# LED_003.net
KiCad netlist of a schematic drawn in EAGLE
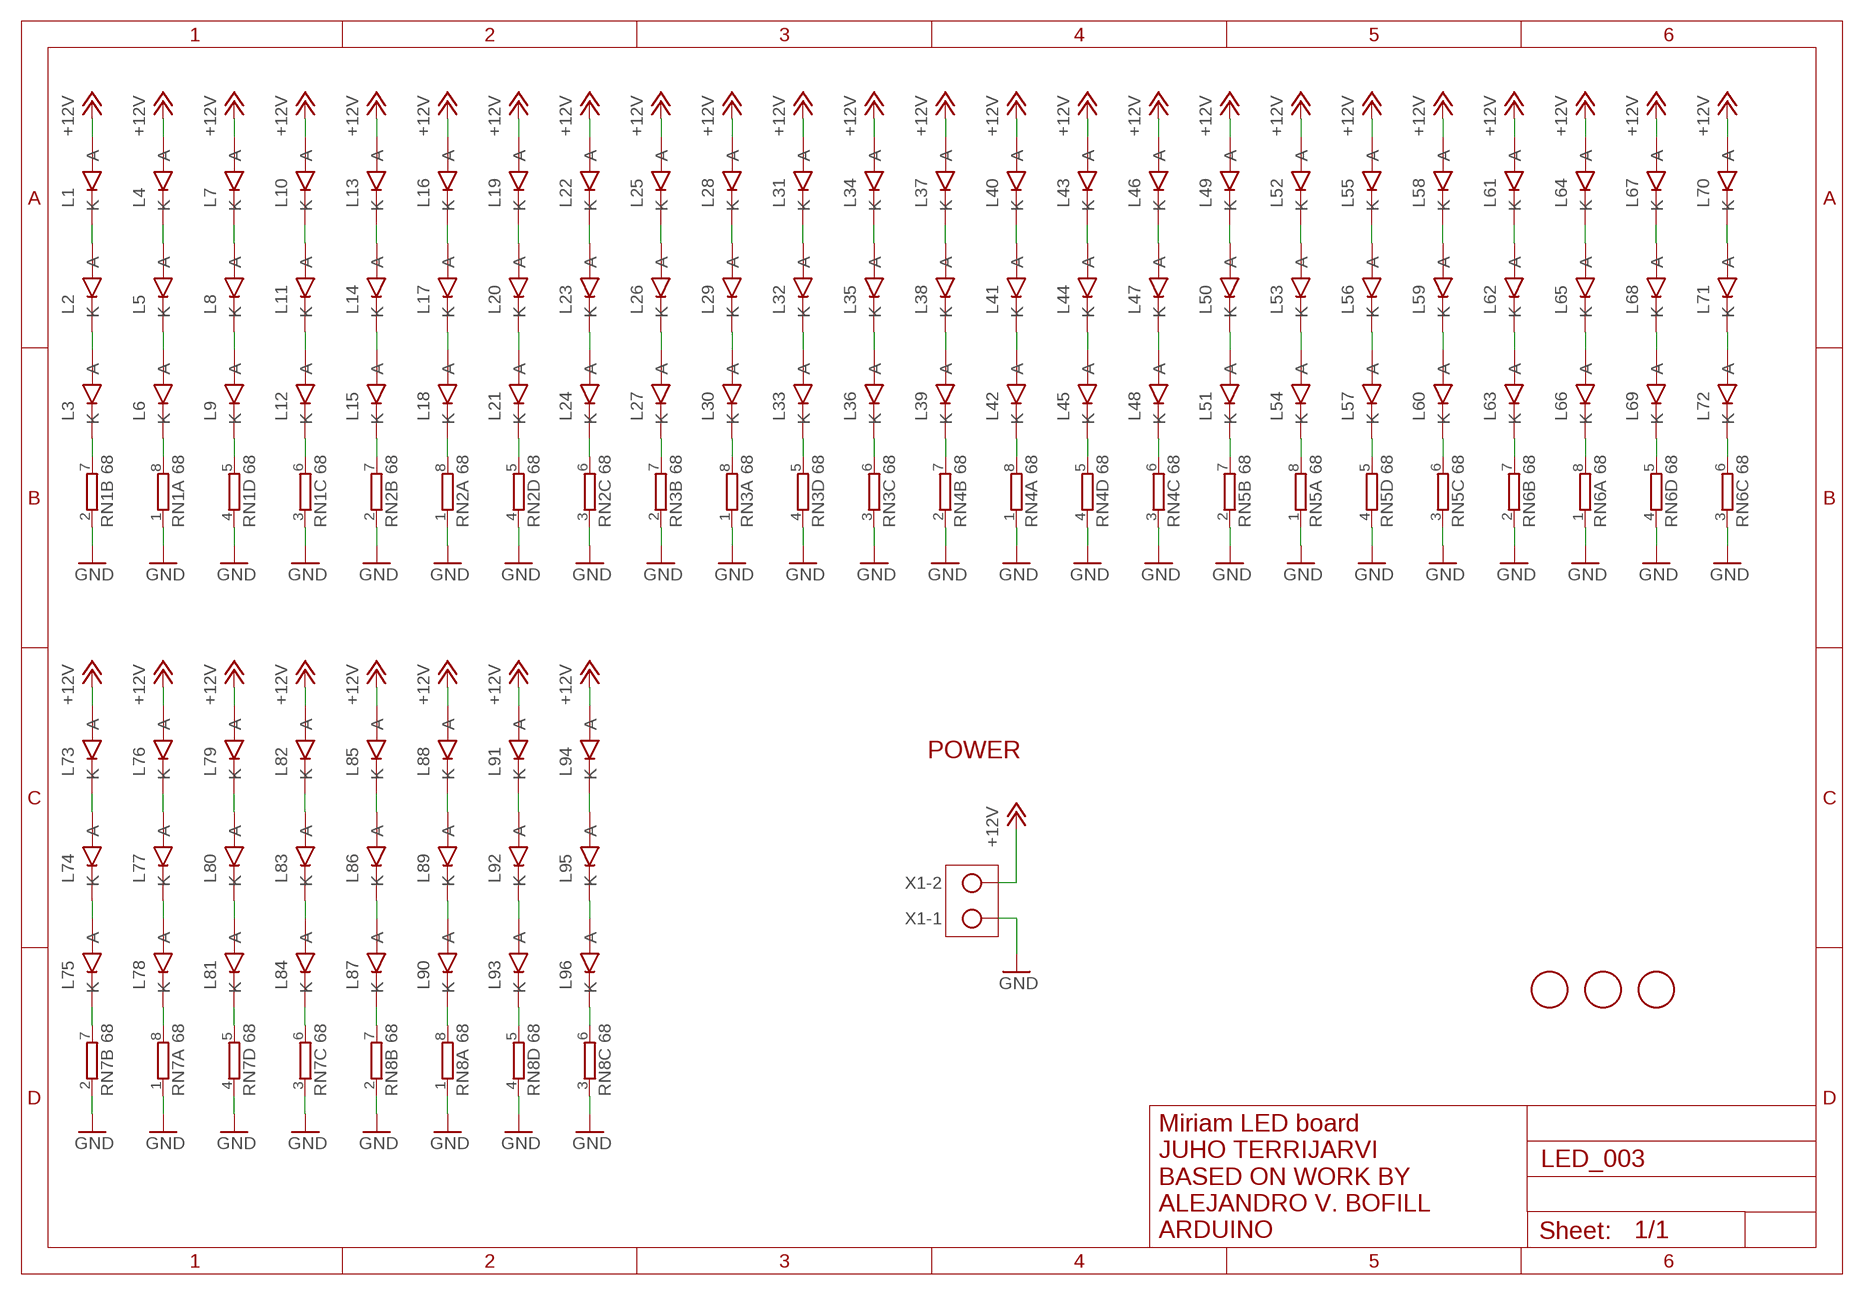
[diagram p0: schematic, sheet 1]

(export (version "E")
  (design (tool "Eeschema 10.0.6"))
  (components
    (comp (ref "FD1")
      (value "FIDUCIALMOUNT")
      (footprint "eagle-import:FIDUCIA-MOUNT")
      (libsource (lib "eagle-import") (part "FIDUCIALMOUNT"))
    )
    (comp (ref "FD2")
      (value "FIDUCIALMOUNT")
      (footprint "eagle-import:FIDUCIA-MOUNT")
      (libsource (lib "eagle-import") (part "FIDUCIALMOUNT"))
    )
    (comp (ref "FD3")
      (value "FIDUCIALMOUNT")
      (footprint "eagle-import:FIDUCIA-MOUNT")
      (libsource (lib "eagle-import") (part "FIDUCIALMOUNT"))
    )
    (comp (ref "L1")
      (value "KA-2810AQBS-G")
      (footprint "eagle-import:LED_0.2")
      (libsource (lib "eagle-import") (part "LED_0.2"))
    )
    (comp (ref "L2")
      (value "KA-2810AQBS-G")
      (footprint "eagle-import:LED_0.2")
      (libsource (lib "eagle-import") (part "LED_0.2"))
    )
    (comp (ref "L3")
      (value "KA-2810AQBS-G")
      (footprint "eagle-import:LED_0.2")
      (libsource (lib "eagle-import") (part "LED_0.2"))
    )
    (comp (ref "L4")
      (value "KA-2810AQBS-G")
      (footprint "eagle-import:LED_0.2")
      (libsource (lib "eagle-import") (part "LED_0.2"))
    )
    (comp (ref "L5")
      (value "KA-2810AQBS-G")
      (footprint "eagle-import:LED_0.2")
      (libsource (lib "eagle-import") (part "LED_0.2"))
    )
    (comp (ref "L6")
      (value "KA-2810AQBS-G")
      (footprint "eagle-import:LED_0.2")
      (libsource (lib "eagle-import") (part "LED_0.2"))
    )
    (comp (ref "L7")
      (value "KA-2810AQBS-G")
      (footprint "eagle-import:LED_0.2")
      (libsource (lib "eagle-import") (part "LED_0.2"))
    )
    (comp (ref "L8")
      (value "KA-2810AQBS-G")
      (footprint "eagle-import:LED_0.2")
      (libsource (lib "eagle-import") (part "LED_0.2"))
    )
    (comp (ref "L9")
      (value "KA-2810AQBS-G")
      (footprint "eagle-import:LED_0.2")
      (libsource (lib "eagle-import") (part "LED_0.2"))
    )
    (comp (ref "L10")
      (value "KA-2810AQBS-G")
      (footprint "eagle-import:LED_0.2")
      (libsource (lib "eagle-import") (part "LED_0.2"))
    )
    (comp (ref "L11")
      (value "KA-2810AQBS-G")
      (footprint "eagle-import:LED_0.2")
      (libsource (lib "eagle-import") (part "LED_0.2"))
    )
    (comp (ref "L12")
      (value "KA-2810AQBS-G")
      (footprint "eagle-import:LED_0.2")
      (libsource (lib "eagle-import") (part "LED_0.2"))
    )
    (comp (ref "L13")
      (value "KA-2810AQBS-G")
      (footprint "eagle-import:LED_0.2")
      (libsource (lib "eagle-import") (part "LED_0.2"))
    )
    (comp (ref "L14")
      (value "KA-2810AQBS-G")
      (footprint "eagle-import:LED_0.2")
      (libsource (lib "eagle-import") (part "LED_0.2"))
    )
    (comp (ref "L15")
      (value "KA-2810AQBS-G")
      (footprint "eagle-import:LED_0.2")
      (libsource (lib "eagle-import") (part "LED_0.2"))
    )
    (comp (ref "L16")
      (value "KA-2810AQBS-G")
      (footprint "eagle-import:LED_0.2")
      (libsource (lib "eagle-import") (part "LED_0.2"))
    )
    (comp (ref "L17")
      (value "KA-2810AQBS-G")
      (footprint "eagle-import:LED_0.2")
      (libsource (lib "eagle-import") (part "LED_0.2"))
    )
    (comp (ref "L18")
      (value "KA-2810AQBS-G")
      (footprint "eagle-import:LED_0.2")
      (libsource (lib "eagle-import") (part "LED_0.2"))
    )
    (comp (ref "L19")
      (value "KA-2810AQBS-G")
      (footprint "eagle-import:LED_0.2")
      (libsource (lib "eagle-import") (part "LED_0.2"))
    )
    (comp (ref "L20")
      (value "KA-2810AQBS-G")
      (footprint "eagle-import:LED_0.2")
      (libsource (lib "eagle-import") (part "LED_0.2"))
    )
    (comp (ref "L21")
      (value "KA-2810AQBS-G")
      (footprint "eagle-import:LED_0.2")
      (libsource (lib "eagle-import") (part "LED_0.2"))
    )
    (comp (ref "L22")
      (value "KA-2810AQBS-G")
      (footprint "eagle-import:LED_0.2")
      (libsource (lib "eagle-import") (part "LED_0.2"))
    )
    (comp (ref "L23")
      (value "KA-2810AQBS-G")
      (footprint "eagle-import:LED_0.2")
      (libsource (lib "eagle-import") (part "LED_0.2"))
    )
    (comp (ref "L24")
      (value "KA-2810AQBS-G")
      (footprint "eagle-import:LED_0.2")
      (libsource (lib "eagle-import") (part "LED_0.2"))
    )
    (comp (ref "L25")
      (value "KA-2810AQBS-G")
      (footprint "eagle-import:LED_0.2")
      (libsource (lib "eagle-import") (part "LED_0.2"))
    )
    (comp (ref "L26")
      (value "KA-2810AQBS-G")
      (footprint "eagle-import:LED_0.2")
      (libsource (lib "eagle-import") (part "LED_0.2"))
    )
    (comp (ref "L27")
      (value "KA-2810AQBS-G")
      (footprint "eagle-import:LED_0.2")
      (libsource (lib "eagle-import") (part "LED_0.2"))
    )
    (comp (ref "L28")
      (value "KA-2810AQBS-G")
      (footprint "eagle-import:LED_0.2")
      (libsource (lib "eagle-import") (part "LED_0.2"))
    )
    (comp (ref "L29")
      (value "KA-2810AQBS-G")
      (footprint "eagle-import:LED_0.2")
      (libsource (lib "eagle-import") (part "LED_0.2"))
    )
    (comp (ref "L30")
      (value "KA-2810AQBS-G")
      (footprint "eagle-import:LED_0.2")
      (libsource (lib "eagle-import") (part "LED_0.2"))
    )
    (comp (ref "L31")
      (value "KA-2810AQBS-G")
      (footprint "eagle-import:LED_0.2")
      (libsource (lib "eagle-import") (part "LED_0.2"))
    )
    (comp (ref "L32")
      (value "KA-2810AQBS-G")
      (footprint "eagle-import:LED_0.2")
      (libsource (lib "eagle-import") (part "LED_0.2"))
    )
    (comp (ref "L33")
      (value "KA-2810AQBS-G")
      (footprint "eagle-import:LED_0.2")
      (libsource (lib "eagle-import") (part "LED_0.2"))
    )
    (comp (ref "L34")
      (value "KA-2810AQBS-G")
      (footprint "eagle-import:LED_0.2")
      (libsource (lib "eagle-import") (part "LED_0.2"))
    )
    (comp (ref "L35")
      (value "KA-2810AQBS-G")
      (footprint "eagle-import:LED_0.2")
      (libsource (lib "eagle-import") (part "LED_0.2"))
    )
    (comp (ref "L36")
      (value "KA-2810AQBS-G")
      (footprint "eagle-import:LED_0.2")
      (libsource (lib "eagle-import") (part "LED_0.2"))
    )
    (comp (ref "L37")
      (value "KA-2810AQBS-G")
      (footprint "eagle-import:LED_0.2")
      (libsource (lib "eagle-import") (part "LED_0.2"))
    )
    (comp (ref "L38")
      (value "KA-2810AQBS-G")
      (footprint "eagle-import:LED_0.2")
      (libsource (lib "eagle-import") (part "LED_0.2"))
    )
    (comp (ref "L39")
      (value "KA-2810AQBS-G")
      (footprint "eagle-import:LED_0.2")
      (libsource (lib "eagle-import") (part "LED_0.2"))
    )
    (comp (ref "L40")
      (value "KA-2810AQBS-G")
      (footprint "eagle-import:LED_0.2")
      (libsource (lib "eagle-import") (part "LED_0.2"))
    )
    (comp (ref "L41")
      (value "KA-2810AQBS-G")
      (footprint "eagle-import:LED_0.2")
      (libsource (lib "eagle-import") (part "LED_0.2"))
    )
    (comp (ref "L42")
      (value "KA-2810AQBS-G")
      (footprint "eagle-import:LED_0.2")
      (libsource (lib "eagle-import") (part "LED_0.2"))
    )
    (comp (ref "L43")
      (value "KA-2810AQBS-G")
      (footprint "eagle-import:LED_0.2")
      (libsource (lib "eagle-import") (part "LED_0.2"))
    )
    (comp (ref "L44")
      (value "KA-2810AQBS-G")
      (footprint "eagle-import:LED_0.2")
      (libsource (lib "eagle-import") (part "LED_0.2"))
    )
    (comp (ref "L45")
      (value "KA-2810AQBS-G")
      (footprint "eagle-import:LED_0.2")
      (libsource (lib "eagle-import") (part "LED_0.2"))
    )
    (comp (ref "L46")
      (value "KA-2810AQBS-G")
      (footprint "eagle-import:LED_0.2")
      (libsource (lib "eagle-import") (part "LED_0.2"))
    )
    (comp (ref "L47")
      (value "KA-2810AQBS-G")
      (footprint "eagle-import:LED_0.2")
      (libsource (lib "eagle-import") (part "LED_0.2"))
    )
    (comp (ref "L48")
      (value "KA-2810AQBS-G")
      (footprint "eagle-import:LED_0.2")
      (libsource (lib "eagle-import") (part "LED_0.2"))
    )
    (comp (ref "L49")
      (value "KA-2810AQBS-G")
      (footprint "eagle-import:LED_0.2")
      (libsource (lib "eagle-import") (part "LED_0.2"))
    )
    (comp (ref "L50")
      (value "KA-2810AQBS-G")
      (footprint "eagle-import:LED_0.2")
      (libsource (lib "eagle-import") (part "LED_0.2"))
    )
    (comp (ref "L51")
      (value "KA-2810AQBS-G")
      (footprint "eagle-import:LED_0.2")
      (libsource (lib "eagle-import") (part "LED_0.2"))
    )
    (comp (ref "L52")
      (value "KA-2810AQBS-G")
      (footprint "eagle-import:LED_0.2")
      (libsource (lib "eagle-import") (part "LED_0.2"))
    )
    (comp (ref "L53")
      (value "KA-2810AQBS-G")
      (footprint "eagle-import:LED_0.2")
      (libsource (lib "eagle-import") (part "LED_0.2"))
    )
    (comp (ref "L54")
      (value "KA-2810AQBS-G")
      (footprint "eagle-import:LED_0.2")
      (libsource (lib "eagle-import") (part "LED_0.2"))
    )
    (comp (ref "L55")
      (value "KA-2810AQBS-G")
      (footprint "eagle-import:LED_0.2")
      (libsource (lib "eagle-import") (part "LED_0.2"))
    )
    (comp (ref "L56")
      (value "KA-2810AQBS-G")
      (footprint "eagle-import:LED_0.2")
      (libsource (lib "eagle-import") (part "LED_0.2"))
    )
    (comp (ref "L57")
      (value "KA-2810AQBS-G")
      (footprint "eagle-import:LED_0.2")
      (libsource (lib "eagle-import") (part "LED_0.2"))
    )
    (comp (ref "L58")
      (value "KA-2810AQBS-G")
      (footprint "eagle-import:LED_0.2")
      (libsource (lib "eagle-import") (part "LED_0.2"))
    )
    (comp (ref "L59")
      (value "KA-2810AQBS-G")
      (footprint "eagle-import:LED_0.2")
      (libsource (lib "eagle-import") (part "LED_0.2"))
    )
    (comp (ref "L60")
      (value "KA-2810AQBS-G")
      (footprint "eagle-import:LED_0.2")
      (libsource (lib "eagle-import") (part "LED_0.2"))
    )
    (comp (ref "L61")
      (value "KA-2810AQBS-G")
      (footprint "eagle-import:LED_0.2")
      (libsource (lib "eagle-import") (part "LED_0.2"))
    )
    (comp (ref "L62")
      (value "KA-2810AQBS-G")
      (footprint "eagle-import:LED_0.2")
      (libsource (lib "eagle-import") (part "LED_0.2"))
    )
    (comp (ref "L63")
      (value "KA-2810AQBS-G")
      (footprint "eagle-import:LED_0.2")
      (libsource (lib "eagle-import") (part "LED_0.2"))
    )
    (comp (ref "L64")
      (value "KA-2810AQBS-G")
      (footprint "eagle-import:LED_0.2")
      (libsource (lib "eagle-import") (part "LED_0.2"))
    )
    (comp (ref "L65")
      (value "KA-2810AQBS-G")
      (footprint "eagle-import:LED_0.2")
      (libsource (lib "eagle-import") (part "LED_0.2"))
    )
    (comp (ref "L66")
      (value "KA-2810AQBS-G")
      (footprint "eagle-import:LED_0.2")
      (libsource (lib "eagle-import") (part "LED_0.2"))
    )
    (comp (ref "L67")
      (value "KA-2810AQBS-G")
      (footprint "eagle-import:LED_0.2")
      (libsource (lib "eagle-import") (part "LED_0.2"))
    )
    (comp (ref "L68")
      (value "KA-2810AQBS-G")
      (footprint "eagle-import:LED_0.2")
      (libsource (lib "eagle-import") (part "LED_0.2"))
    )
    (comp (ref "L69")
      (value "KA-2810AQBS-G")
      (footprint "eagle-import:LED_0.2")
      (libsource (lib "eagle-import") (part "LED_0.2"))
    )
    (comp (ref "L70")
      (value "KA-2810AQBS-G")
      (footprint "eagle-import:LED_0.2")
      (libsource (lib "eagle-import") (part "LED_0.2"))
    )
    (comp (ref "L71")
      (value "KA-2810AQBS-G")
      (footprint "eagle-import:LED_0.2")
      (libsource (lib "eagle-import") (part "LED_0.2"))
    )
    (comp (ref "L72")
      (value "KA-2810AQBS-G")
      (footprint "eagle-import:LED_0.2")
      (libsource (lib "eagle-import") (part "LED_0.2"))
    )
    (comp (ref "L73")
      (value "KA-2810AQBS-G")
      (footprint "eagle-import:LED_0.2")
      (libsource (lib "eagle-import") (part "LED_0.2"))
    )
    (comp (ref "L74")
      (value "KA-2810AQBS-G")
      (footprint "eagle-import:LED_0.2")
      (libsource (lib "eagle-import") (part "LED_0.2"))
    )
    (comp (ref "L75")
      (value "KA-2810AQBS-G")
      (footprint "eagle-import:LED_0.2")
      (libsource (lib "eagle-import") (part "LED_0.2"))
    )
    (comp (ref "L76")
      (value "KA-2810AQBS-G")
      (footprint "eagle-import:LED_0.2")
      (libsource (lib "eagle-import") (part "LED_0.2"))
    )
    (comp (ref "L77")
      (value "KA-2810AQBS-G")
      (footprint "eagle-import:LED_0.2")
      (libsource (lib "eagle-import") (part "LED_0.2"))
    )
    (comp (ref "L78")
      (value "KA-2810AQBS-G")
      (footprint "eagle-import:LED_0.2")
      (libsource (lib "eagle-import") (part "LED_0.2"))
    )
    (comp (ref "L79")
      (value "KA-2810AQBS-G")
      (footprint "eagle-import:LED_0.2")
      (libsource (lib "eagle-import") (part "LED_0.2"))
    )
    (comp (ref "L80")
      (value "KA-2810AQBS-G")
      (footprint "eagle-import:LED_0.2")
      (libsource (lib "eagle-import") (part "LED_0.2"))
    )
    (comp (ref "L81")
      (value "KA-2810AQBS-G")
      (footprint "eagle-import:LED_0.2")
      (libsource (lib "eagle-import") (part "LED_0.2"))
    )
    (comp (ref "L82")
      (value "KA-2810AQBS-G")
      (footprint "eagle-import:LED_0.2")
      (libsource (lib "eagle-import") (part "LED_0.2"))
    )
    (comp (ref "L83")
      (value "KA-2810AQBS-G")
      (footprint "eagle-import:LED_0.2")
      (libsource (lib "eagle-import") (part "LED_0.2"))
    )
    (comp (ref "L84")
      (value "KA-2810AQBS-G")
      (footprint "eagle-import:LED_0.2")
      (libsource (lib "eagle-import") (part "LED_0.2"))
    )
    (comp (ref "L85")
      (value "KA-2810AQBS-G")
      (footprint "eagle-import:LED_0.2")
      (libsource (lib "eagle-import") (part "LED_0.2"))
    )
    (comp (ref "L86")
      (value "KA-2810AQBS-G")
      (footprint "eagle-import:LED_0.2")
      (libsource (lib "eagle-import") (part "LED_0.2"))
    )
    (comp (ref "L87")
      (value "KA-2810AQBS-G")
      (footprint "eagle-import:LED_0.2")
      (libsource (lib "eagle-import") (part "LED_0.2"))
    )
    (comp (ref "L88")
      (value "KA-2810AQBS-G")
      (footprint "eagle-import:LED_0.2")
      (libsource (lib "eagle-import") (part "LED_0.2"))
    )
    (comp (ref "L89")
      (value "KA-2810AQBS-G")
      (footprint "eagle-import:LED_0.2")
      (libsource (lib "eagle-import") (part "LED_0.2"))
    )
    (comp (ref "L90")
      (value "KA-2810AQBS-G")
      (footprint "eagle-import:LED_0.2")
      (libsource (lib "eagle-import") (part "LED_0.2"))
    )
    (comp (ref "L91")
      (value "KA-2810AQBS-G")
      (footprint "eagle-import:LED_0.2")
      (libsource (lib "eagle-import") (part "LED_0.2"))
    )
    (comp (ref "L92")
      (value "KA-2810AQBS-G")
      (footprint "eagle-import:LED_0.2")
      (libsource (lib "eagle-import") (part "LED_0.2"))
    )
    (comp (ref "L93")
      (value "KA-2810AQBS-G")
      (footprint "eagle-import:LED_0.2")
      (libsource (lib "eagle-import") (part "LED_0.2"))
    )
    (comp (ref "L94")
      (value "KA-2810AQBS-G")
      (footprint "eagle-import:LED_0.2")
      (libsource (lib "eagle-import") (part "LED_0.2"))
    )
    (comp (ref "L95")
      (value "KA-2810AQBS-G")
      (footprint "eagle-import:LED_0.2")
      (libsource (lib "eagle-import") (part "LED_0.2"))
    )
    (comp (ref "L96")
      (value "KA-2810AQBS-G")
      (footprint "eagle-import:LED_0.2")
      (libsource (lib "eagle-import") (part "LED_0.2"))
    )
    (comp (ref "RN1")
      (value "68")
      (footprint "eagle-import:CAY16")
      (libsource (lib "eagle-import") (part "4R-NCAY16"))
    )
    (comp (ref "RN2")
      (value "68")
      (footprint "eagle-import:CAY16")
      (libsource (lib "eagle-import") (part "4R-NCAY16"))
    )
    (comp (ref "RN3")
      (value "68")
      (footprint "eagle-import:CAY16")
      (libsource (lib "eagle-import") (part "4R-NCAY16"))
    )
    (comp (ref "RN4")
      (value "68")
      (footprint "eagle-import:CAY16")
      (libsource (lib "eagle-import") (part "4R-NCAY16"))
    )
    (comp (ref "RN5")
      (value "68")
      (footprint "eagle-import:CAY16")
      (libsource (lib "eagle-import") (part "4R-NCAY16"))
    )
    (comp (ref "RN6")
      (value "68")
      (footprint "eagle-import:CAY16")
      (libsource (lib "eagle-import") (part "4R-NCAY16"))
    )
    (comp (ref "RN7")
      (value "68")
      (footprint "eagle-import:CAY16")
      (libsource (lib "eagle-import") (part "4R-NCAY16"))
    )
    (comp (ref "RN8")
      (value "68")
      (footprint "eagle-import:CAY16")
      (libsource (lib "eagle-import") (part "4R-NCAY16"))
    )
    (comp (ref "X1")
      (value "MKDSN1,5/2-5,08")
      (footprint "eagle-import:MKDSN1,5_2-5,08")
      (libsource (lib "eagle-import") (part "MKDSN1,5/2-5,08"))
    )
  )
  (nets
    (net (code "1") (name "+12V") (class "Default")
      (node (ref "L1") (pin "2") (pinfunction "A_2") (pintype "input"))
      (node (ref "L10") (pin "2") (pinfunction "A_2") (pintype "input"))
      (node (ref "L13") (pin "2") (pinfunction "A_2") (pintype "input"))
      (node (ref "L16") (pin "2") (pinfunction "A_2") (pintype "input"))
      (node (ref "L19") (pin "2") (pinfunction "A_2") (pintype "input"))
      (node (ref "L22") (pin "2") (pinfunction "A_2") (pintype "input"))
      (node (ref "L25") (pin "2") (pinfunction "A_2") (pintype "input"))
      (node (ref "L28") (pin "2") (pinfunction "A_2") (pintype "input"))
      (node (ref "L31") (pin "2") (pinfunction "A_2") (pintype "input"))
      (node (ref "L34") (pin "2") (pinfunction "A_2") (pintype "input"))
      (node (ref "L37") (pin "2") (pinfunction "A_2") (pintype "input"))
      (node (ref "L4") (pin "2") (pinfunction "A_2") (pintype "input"))
      (node (ref "L40") (pin "2") (pinfunction "A_2") (pintype "input"))
      (node (ref "L43") (pin "2") (pinfunction "A_2") (pintype "input"))
      (node (ref "L46") (pin "2") (pinfunction "A_2") (pintype "input"))
      (node (ref "L49") (pin "2") (pinfunction "A_2") (pintype "input"))
      (node (ref "L52") (pin "2") (pinfunction "A_2") (pintype "input"))
      (node (ref "L55") (pin "2") (pinfunction "A_2") (pintype "input"))
      (node (ref "L58") (pin "2") (pinfunction "A_2") (pintype "input"))
      (node (ref "L61") (pin "2") (pinfunction "A_2") (pintype "input"))
      (node (ref "L64") (pin "2") (pinfunction "A_2") (pintype "input"))
      (node (ref "L67") (pin "2") (pinfunction "A_2") (pintype "input"))
      (node (ref "L7") (pin "2") (pinfunction "A_2") (pintype "input"))
      (node (ref "L70") (pin "2") (pinfunction "A_2") (pintype "input"))
      (node (ref "L73") (pin "2") (pinfunction "A_2") (pintype "input"))
      (node (ref "L76") (pin "2") (pinfunction "A_2") (pintype "input"))
      (node (ref "L79") (pin "2") (pinfunction "A_2") (pintype "input"))
      (node (ref "L82") (pin "2") (pinfunction "A_2") (pintype "input"))
      (node (ref "L85") (pin "2") (pinfunction "A_2") (pintype "input"))
      (node (ref "L88") (pin "2") (pinfunction "A_2") (pintype "input"))
      (node (ref "L91") (pin "2") (pinfunction "A_2") (pintype "input"))
      (node (ref "L94") (pin "2") (pinfunction "A_2") (pintype "input"))
      (node (ref "X1") (pin "2") (pinfunction "KL_2") (pintype "passive"))
    )
    (net (code "2") (name "GND") (class "Default")
      (node (ref "RN1") (pin "1") (pinfunction "1_1") (pintype "passive"))
      (node (ref "RN1") (pin "2") (pinfunction "1_2") (pintype "passive"))
      (node (ref "RN1") (pin "3") (pinfunction "1_3") (pintype "passive"))
      (node (ref "RN1") (pin "4") (pinfunction "1_4") (pintype "passive"))
      (node (ref "RN2") (pin "1") (pinfunction "1_1") (pintype "passive"))
      (node (ref "RN2") (pin "2") (pinfunction "1_2") (pintype "passive"))
      (node (ref "RN2") (pin "3") (pinfunction "1_3") (pintype "passive"))
      (node (ref "RN2") (pin "4") (pinfunction "1_4") (pintype "passive"))
      (node (ref "RN3") (pin "1") (pinfunction "1_1") (pintype "passive"))
      (node (ref "RN3") (pin "2") (pinfunction "1_2") (pintype "passive"))
      (node (ref "RN3") (pin "3") (pinfunction "1_3") (pintype "passive"))
      (node (ref "RN3") (pin "4") (pinfunction "1_4") (pintype "passive"))
      (node (ref "RN4") (pin "1") (pinfunction "1_1") (pintype "passive"))
      (node (ref "RN4") (pin "2") (pinfunction "1_2") (pintype "passive"))
      (node (ref "RN4") (pin "3") (pinfunction "1_3") (pintype "passive"))
      (node (ref "RN4") (pin "4") (pinfunction "1_4") (pintype "passive"))
      (node (ref "RN5") (pin "1") (pinfunction "1_1") (pintype "passive"))
      (node (ref "RN5") (pin "2") (pinfunction "1_2") (pintype "passive"))
      (node (ref "RN5") (pin "3") (pinfunction "1_3") (pintype "passive"))
      (node (ref "RN5") (pin "4") (pinfunction "1_4") (pintype "passive"))
      (node (ref "RN6") (pin "1") (pinfunction "1_1") (pintype "passive"))
      (node (ref "RN6") (pin "2") (pinfunction "1_2") (pintype "passive"))
      (node (ref "RN6") (pin "3") (pinfunction "1_3") (pintype "passive"))
      (node (ref "RN6") (pin "4") (pinfunction "1_4") (pintype "passive"))
      (node (ref "RN7") (pin "1") (pinfunction "1_1") (pintype "passive"))
      (node (ref "RN7") (pin "2") (pinfunction "1_2") (pintype "passive"))
      (node (ref "RN7") (pin "3") (pinfunction "1_3") (pintype "passive"))
      (node (ref "RN7") (pin "4") (pinfunction "1_4") (pintype "passive"))
      (node (ref "RN8") (pin "1") (pinfunction "1_1") (pintype "passive"))
      (node (ref "RN8") (pin "2") (pinfunction "1_2") (pintype "passive"))
      (node (ref "RN8") (pin "3") (pinfunction "1_3") (pintype "passive"))
      (node (ref "RN8") (pin "4") (pinfunction "1_4") (pintype "passive"))
      (node (ref "X1") (pin "1") (pinfunction "KL_1") (pintype "passive"))
    )
    (net (code "3") (name "Net-(L1-K)") (class "Default")
      (node (ref "L1") (pin "1") (pinfunction "K_1") (pintype "output"))
      (node (ref "L2") (pin "2") (pinfunction "A_2") (pintype "input"))
    )
    (net (code "4") (name "Net-(L2-K)") (class "Default")
      (node (ref "L2") (pin "1") (pinfunction "K_1") (pintype "output"))
      (node (ref "L3") (pin "2") (pinfunction "A_2") (pintype "input"))
    )
    (net (code "5") (name "Net-(L3-K)") (class "Default")
      (node (ref "L3") (pin "1") (pinfunction "K_1") (pintype "output"))
      (node (ref "RN1") (pin "7") (pinfunction "2_7") (pintype "passive"))
    )
    (net (code "6") (name "Net-(L4-K)") (class "Default")
      (node (ref "L4") (pin "1") (pinfunction "K_1") (pintype "output"))
      (node (ref "L5") (pin "2") (pinfunction "A_2") (pintype "input"))
    )
    (net (code "7") (name "Net-(L5-K)") (class "Default")
      (node (ref "L5") (pin "1") (pinfunction "K_1") (pintype "output"))
      (node (ref "L6") (pin "2") (pinfunction "A_2") (pintype "input"))
    )
    (net (code "8") (name "Net-(L6-K)") (class "Default")
      (node (ref "L6") (pin "1") (pinfunction "K_1") (pintype "output"))
      (node (ref "RN1") (pin "8") (pinfunction "2_8") (pintype "passive"))
    )
    (net (code "9") (name "Net-(L7-K)") (class "Default")
      (node (ref "L7") (pin "1") (pinfunction "K_1") (pintype "output"))
      (node (ref "L8") (pin "2") (pinfunction "A_2") (pintype "input"))
    )
    (net (code "10") (name "Net-(L8-K)") (class "Default")
      (node (ref "L8") (pin "1") (pinfunction "K_1") (pintype "output"))
      (node (ref "L9") (pin "2") (pinfunction "A_2") (pintype "input"))
    )
    (net (code "11") (name "Net-(L9-K)") (class "Default")
      (node (ref "L9") (pin "1") (pinfunction "K_1") (pintype "output"))
      (node (ref "RN1") (pin "5") (pinfunction "2_5") (pintype "passive"))
    )
    (net (code "12") (name "Net-(L10-K)") (class "Default")
      (node (ref "L10") (pin "1") (pinfunction "K_1") (pintype "output"))
      (node (ref "L11") (pin "2") (pinfunction "A_2") (pintype "input"))
    )
    (net (code "13") (name "Net-(L11-K)") (class "Default")
      (node (ref "L11") (pin "1") (pinfunction "K_1") (pintype "output"))
      (node (ref "L12") (pin "2") (pinfunction "A_2") (pintype "input"))
    )
    (net (code "14") (name "Net-(L12-K)") (class "Default")
      (node (ref "L12") (pin "1") (pinfunction "K_1") (pintype "output"))
      (node (ref "RN1") (pin "6") (pinfunction "2_6") (pintype "passive"))
    )
    (net (code "15") (name "Net-(L13-K)") (class "Default")
      (node (ref "L13") (pin "1") (pinfunction "K_1") (pintype "output"))
      (node (ref "L14") (pin "2") (pinfunction "A_2") (pintype "input"))
    )
    (net (code "16") (name "Net-(L14-K)") (class "Default")
      (node (ref "L14") (pin "1") (pinfunction "K_1") (pintype "output"))
      (node (ref "L15") (pin "2") (pinfunction "A_2") (pintype "input"))
    )
    (net (code "17") (name "Net-(L15-K)") (class "Default")
      (node (ref "L15") (pin "1") (pinfunction "K_1") (pintype "output"))
      (node (ref "RN2") (pin "7") (pinfunction "2_7") (pintype "passive"))
    )
    (net (code "18") (name "Net-(L16-K)") (class "Default")
      (node (ref "L16") (pin "1") (pinfunction "K_1") (pintype "output"))
      (node (ref "L17") (pin "2") (pinfunction "A_2") (pintype "input"))
    )
    (net (code "19") (name "Net-(L17-K)") (class "Default")
      (node (ref "L17") (pin "1") (pinfunction "K_1") (pintype "output"))
      (node (ref "L18") (pin "2") (pinfunction "A_2") (pintype "input"))
    )
    (net (code "20") (name "Net-(L18-K)") (class "Default")
      (node (ref "L18") (pin "1") (pinfunction "K_1") (pintype "output"))
      (node (ref "RN2") (pin "8") (pinfunction "2_8") (pintype "passive"))
    )
    (net (code "21") (name "Net-(L19-K)") (class "Default")
      (node (ref "L19") (pin "1") (pinfunction "K_1") (pintype "output"))
      (node (ref "L20") (pin "2") (pinfunction "A_2") (pintype "input"))
    )
    (net (code "22") (name "Net-(L20-K)") (class "Default")
      (node (ref "L20") (pin "1") (pinfunction "K_1") (pintype "output"))
      (node (ref "L21") (pin "2") (pinfunction "A_2") (pintype "input"))
    )
    (net (code "23") (name "Net-(L21-K)") (class "Default")
      (node (ref "L21") (pin "1") (pinfunction "K_1") (pintype "output"))
      (node (ref "RN2") (pin "5") (pinfunction "2_5") (pintype "passive"))
    )
    (net (code "24") (name "Net-(L22-K)") (class "Default")
      (node (ref "L22") (pin "1") (pinfunction "K_1") (pintype "output"))
      (node (ref "L23") (pin "2") (pinfunction "A_2") (pintype "input"))
    )
    (net (code "25") (name "Net-(L23-K)") (class "Default")
      (node (ref "L23") (pin "1") (pinfunction "K_1") (pintype "output"))
      (node (ref "L24") (pin "2") (pinfunction "A_2") (pintype "input"))
    )
    (net (code "26") (name "Net-(L24-K)") (class "Default")
      (node (ref "L24") (pin "1") (pinfunction "K_1") (pintype "output"))
      (node (ref "RN2") (pin "6") (pinfunction "2_6") (pintype "passive"))
    )
    (net (code "27") (name "Net-(L25-K)") (class "Default")
      (node (ref "L25") (pin "1") (pinfunction "K_1") (pintype "output"))
      (node (ref "L26") (pin "2") (pinfunction "A_2") (pintype "input"))
    )
    (net (code "28") (name "Net-(L26-K)") (class "Default")
      (node (ref "L26") (pin "1") (pinfunction "K_1") (pintype "output"))
      (node (ref "L27") (pin "2") (pinfunction "A_2") (pintype "input"))
    )
    (net (code "29") (name "Net-(L27-K)") (class "Default")
      (node (ref "L27") (pin "1") (pinfunction "K_1") (pintype "output"))
      (node (ref "RN3") (pin "7") (pinfunction "2_7") (pintype "passive"))
    )
    (net (code "30") (name "Net-(L28-K)") (class "Default")
      (node (ref "L28") (pin "1") (pinfunction "K_1") (pintype "output"))
      (node (ref "L29") (pin "2") (pinfunction "A_2") (pintype "input"))
    )
    (net (code "31") (name "Net-(L29-K)") (class "Default")
      (node (ref "L29") (pin "1") (pinfunction "K_1") (pintype "output"))
      (node (ref "L30") (pin "2") (pinfunction "A_2") (pintype "input"))
    )
    (net (code "32") (name "Net-(L30-K)") (class "Default")
      (node (ref "L30") (pin "1") (pinfunction "K_1") (pintype "output"))
      (node (ref "RN3") (pin "8") (pinfunction "2_8") (pintype "passive"))
    )
    (net (code "33") (name "Net-(L31-K)") (class "Default")
      (node (ref "L31") (pin "1") (pinfunction "K_1") (pintype "output"))
      (node (ref "L32") (pin "2") (pinfunction "A_2") (pintype "input"))
    )
    (net (code "34") (name "Net-(L32-K)") (class "Default")
      (node (ref "L32") (pin "1") (pinfunction "K_1") (pintype "output"))
      (node (ref "L33") (pin "2") (pinfunction "A_2") (pintype "input"))
    )
    (net (code "35") (name "Net-(L33-K)") (class "Default")
      (node (ref "L33") (pin "1") (pinfunction "K_1") (pintype "output"))
      (node (ref "RN3") (pin "5") (pinfunction "2_5") (pintype "passive"))
    )
    (net (code "36") (name "Net-(L34-K)") (class "Default")
      (node (ref "L34") (pin "1") (pinfunction "K_1") (pintype "output"))
      (node (ref "L35") (pin "2") (pinfunction "A_2") (pintype "input"))
    )
    (net (code "37") (name "Net-(L35-K)") (class "Default")
      (node (ref "L35") (pin "1") (pinfunction "K_1") (pintype "output"))
      (node (ref "L36") (pin "2") (pinfunction "A_2") (pintype "input"))
    )
    (net (code "38") (name "Net-(L36-K)") (class "Default")
      (node (ref "L36") (pin "1") (pinfunction "K_1") (pintype "output"))
      (node (ref "RN3") (pin "6") (pinfunction "2_6") (pintype "passive"))
    )
    (net (code "39") (name "Net-(L37-K)") (class "Default")
      (node (ref "L37") (pin "1") (pinfunction "K_1") (pintype "output"))
      (node (ref "L38") (pin "2") (pinfunction "A_2") (pintype "input"))
    )
    (net (code "40") (name "Net-(L38-K)") (class "Default")
      (node (ref "L38") (pin "1") (pinfunction "K_1") (pintype "output"))
      (node (ref "L39") (pin "2") (pinfunction "A_2") (pintype "input"))
    )
    (net (code "41") (name "Net-(L39-K)") (class "Default")
      (node (ref "L39") (pin "1") (pinfunction "K_1") (pintype "output"))
      (node (ref "RN4") (pin "7") (pinfunction "2_7") (pintype "passive"))
    )
    (net (code "42") (name "Net-(L40-K)") (class "Default")
      (node (ref "L40") (pin "1") (pinfunction "K_1") (pintype "output"))
      (node (ref "L41") (pin "2") (pinfunction "A_2") (pintype "input"))
    )
    (net (code "43") (name "Net-(L41-K)") (class "Default")
      (node (ref "L41") (pin "1") (pinfunction "K_1") (pintype "output"))
      (node (ref "L42") (pin "2") (pinfunction "A_2") (pintype "input"))
    )
    (net (code "44") (name "Net-(L42-K)") (class "Default")
      (node (ref "L42") (pin "1") (pinfunction "K_1") (pintype "output"))
      (node (ref "RN4") (pin "8") (pinfunction "2_8") (pintype "passive"))
    )
    (net (code "45") (name "Net-(L43-K)") (class "Default")
      (node (ref "L43") (pin "1") (pinfunction "K_1") (pintype "output"))
      (node (ref "L44") (pin "2") (pinfunction "A_2") (pintype "input"))
    )
    (net (code "46") (name "Net-(L44-K)") (class "Default")
      (node (ref "L44") (pin "1") (pinfunction "K_1") (pintype "output"))
      (node (ref "L45") (pin "2") (pinfunction "A_2") (pintype "input"))
    )
    (net (code "47") (name "Net-(L45-K)") (class "Default")
      (node (ref "L45") (pin "1") (pinfunction "K_1") (pintype "output"))
      (node (ref "RN4") (pin "5") (pinfunction "2_5") (pintype "passive"))
    )
    (net (code "48") (name "Net-(L46-K)") (class "Default")
      (node (ref "L46") (pin "1") (pinfunction "K_1") (pintype "output"))
      (node (ref "L47") (pin "2") (pinfunction "A_2") (pintype "input"))
    )
    (net (code "49") (name "Net-(L47-K)") (class "Default")
      (node (ref "L47") (pin "1") (pinfunction "K_1") (pintype "output"))
      (node (ref "L48") (pin "2") (pinfunction "A_2") (pintype "input"))
    )
    (net (code "50") (name "Net-(L48-K)") (class "Default")
      (node (ref "L48") (pin "1") (pinfunction "K_1") (pintype "output"))
      (node (ref "RN4") (pin "6") (pinfunction "2_6") (pintype "passive"))
    )
    (net (code "51") (name "Net-(L49-K)") (class "Default")
      (node (ref "L49") (pin "1") (pinfunction "K_1") (pintype "output"))
      (node (ref "L50") (pin "2") (pinfunction "A_2") (pintype "input"))
    )
    (net (code "52") (name "Net-(L50-K)") (class "Default")
      (node (ref "L50") (pin "1") (pinfunction "K_1") (pintype "output"))
      (node (ref "L51") (pin "2") (pinfunction "A_2") (pintype "input"))
    )
    (net (code "53") (name "Net-(L51-K)") (class "Default")
      (node (ref "L51") (pin "1") (pinfunction "K_1") (pintype "output"))
      (node (ref "RN5") (pin "7") (pinfunction "2_7") (pintype "passive"))
    )
    (net (code "54") (name "Net-(L52-K)") (class "Default")
      (node (ref "L52") (pin "1") (pinfunction "K_1") (pintype "output"))
      (node (ref "L53") (pin "2") (pinfunction "A_2") (pintype "input"))
    )
    (net (code "55") (name "Net-(L53-K)") (class "Default")
      (node (ref "L53") (pin "1") (pinfunction "K_1") (pintype "output"))
      (node (ref "L54") (pin "2") (pinfunction "A_2") (pintype "input"))
    )
    (net (code "56") (name "Net-(L54-K)") (class "Default")
      (node (ref "L54") (pin "1") (pinfunction "K_1") (pintype "output"))
      (node (ref "RN5") (pin "8") (pinfunction "2_8") (pintype "passive"))
    )
    (net (code "57") (name "Net-(L55-K)") (class "Default")
      (node (ref "L55") (pin "1") (pinfunction "K_1") (pintype "output"))
      (node (ref "L56") (pin "2") (pinfunction "A_2") (pintype "input"))
    )
    (net (code "58") (name "Net-(L56-K)") (class "Default")
      (node (ref "L56") (pin "1") (pinfunction "K_1") (pintype "output"))
      (node (ref "L57") (pin "2") (pinfunction "A_2") (pintype "input"))
    )
    (net (code "59") (name "Net-(L57-K)") (class "Default")
      (node (ref "L57") (pin "1") (pinfunction "K_1") (pintype "output"))
      (node (ref "RN5") (pin "5") (pinfunction "2_5") (pintype "passive"))
    )
    (net (code "60") (name "Net-(L58-K)") (class "Default")
      (node (ref "L58") (pin "1") (pinfunction "K_1") (pintype "output"))
      (node (ref "L59") (pin "2") (pinfunction "A_2") (pintype "input"))
    )
    (net (code "61") (name "Net-(L59-K)") (class "Default")
      (node (ref "L59") (pin "1") (pinfunction "K_1") (pintype "output"))
      (node (ref "L60") (pin "2") (pinfunction "A_2") (pintype "input"))
    )
    (net (code "62") (name "Net-(L60-K)") (class "Default")
      (node (ref "L60") (pin "1") (pinfunction "K_1") (pintype "output"))
      (node (ref "RN5") (pin "6") (pinfunction "2_6") (pintype "passive"))
    )
    (net (code "63") (name "Net-(L61-K)") (class "Default")
      (node (ref "L61") (pin "1") (pinfunction "K_1") (pintype "output"))
      (node (ref "L62") (pin "2") (pinfunction "A_2") (pintype "input"))
    )
    (net (code "64") (name "Net-(L62-K)") (class "Default")
      (node (ref "L62") (pin "1") (pinfunction "K_1") (pintype "output"))
      (node (ref "L63") (pin "2") (pinfunction "A_2") (pintype "input"))
    )
    (net (code "65") (name "Net-(L63-K)") (class "Default")
      (node (ref "L63") (pin "1") (pinfunction "K_1") (pintype "output"))
      (node (ref "RN6") (pin "7") (pinfunction "2_7") (pintype "passive"))
    )
    (net (code "66") (name "Net-(L64-K)") (class "Default")
      (node (ref "L64") (pin "1") (pinfunction "K_1") (pintype "output"))
      (node (ref "L65") (pin "2") (pinfunction "A_2") (pintype "input"))
    )
    (net (code "67") (name "Net-(L65-K)") (class "Default")
      (node (ref "L65") (pin "1") (pinfunction "K_1") (pintype "output"))
      (node (ref "L66") (pin "2") (pinfunction "A_2") (pintype "input"))
    )
    (net (code "68") (name "Net-(L66-K)") (class "Default")
      (node (ref "L66") (pin "1") (pinfunction "K_1") (pintype "output"))
      (node (ref "RN6") (pin "8") (pinfunction "2_8") (pintype "passive"))
    )
    (net (code "69") (name "Net-(L67-K)") (class "Default")
      (node (ref "L67") (pin "1") (pinfunction "K_1") (pintype "output"))
      (node (ref "L68") (pin "2") (pinfunction "A_2") (pintype "input"))
    )
    (net (code "70") (name "Net-(L68-K)") (class "Default")
      (node (ref "L68") (pin "1") (pinfunction "K_1") (pintype "output"))
      (node (ref "L69") (pin "2") (pinfunction "A_2") (pintype "input"))
    )
    (net (code "71") (name "Net-(L69-K)") (class "Default")
      (node (ref "L69") (pin "1") (pinfunction "K_1") (pintype "output"))
      (node (ref "RN6") (pin "5") (pinfunction "2_5") (pintype "passive"))
    )
    (net (code "72") (name "Net-(L70-K)") (class "Default")
      (node (ref "L70") (pin "1") (pinfunction "K_1") (pintype "output"))
      (node (ref "L71") (pin "2") (pinfunction "A_2") (pintype "input"))
    )
    (net (code "73") (name "Net-(L71-K)") (class "Default")
      (node (ref "L71") (pin "1") (pinfunction "K_1") (pintype "output"))
      (node (ref "L72") (pin "2") (pinfunction "A_2") (pintype "input"))
    )
    (net (code "74") (name "Net-(L72-K)") (class "Default")
      (node (ref "L72") (pin "1") (pinfunction "K_1") (pintype "output"))
      (node (ref "RN6") (pin "6") (pinfunction "2_6") (pintype "passive"))
    )
    (net (code "75") (name "Net-(L73-K)") (class "Default")
      (node (ref "L73") (pin "1") (pinfunction "K_1") (pintype "output"))
      (node (ref "L74") (pin "2") (pinfunction "A_2") (pintype "input"))
    )
    (net (code "76") (name "Net-(L74-K)") (class "Default")
      (node (ref "L74") (pin "1") (pinfunction "K_1") (pintype "output"))
      (node (ref "L75") (pin "2") (pinfunction "A_2") (pintype "input"))
    )
    (net (code "77") (name "Net-(L75-K)") (class "Default")
      (node (ref "L75") (pin "1") (pinfunction "K_1") (pintype "output"))
      (node (ref "RN7") (pin "7") (pinfunction "2_7") (pintype "passive"))
    )
    (net (code "78") (name "Net-(L76-K)") (class "Default")
      (node (ref "L76") (pin "1") (pinfunction "K_1") (pintype "output"))
      (node (ref "L77") (pin "2") (pinfunction "A_2") (pintype "input"))
    )
    (net (code "79") (name "Net-(L77-K)") (class "Default")
      (node (ref "L77") (pin "1") (pinfunction "K_1") (pintype "output"))
      (node (ref "L78") (pin "2") (pinfunction "A_2") (pintype "input"))
    )
    (net (code "80") (name "Net-(L78-K)") (class "Default")
      (node (ref "L78") (pin "1") (pinfunction "K_1") (pintype "output"))
      (node (ref "RN7") (pin "8") (pinfunction "2_8") (pintype "passive"))
    )
    (net (code "81") (name "Net-(L79-K)") (class "Default")
      (node (ref "L79") (pin "1") (pinfunction "K_1") (pintype "output"))
      (node (ref "L80") (pin "2") (pinfunction "A_2") (pintype "input"))
    )
    (net (code "82") (name "Net-(L80-K)") (class "Default")
      (node (ref "L80") (pin "1") (pinfunction "K_1") (pintype "output"))
      (node (ref "L81") (pin "2") (pinfunction "A_2") (pintype "input"))
    )
    (net (code "83") (name "Net-(L81-K)") (class "Default")
      (node (ref "L81") (pin "1") (pinfunction "K_1") (pintype "output"))
      (node (ref "RN7") (pin "5") (pinfunction "2_5") (pintype "passive"))
    )
    (net (code "84") (name "Net-(L82-K)") (class "Default")
      (node (ref "L82") (pin "1") (pinfunction "K_1") (pintype "output"))
      (node (ref "L83") (pin "2") (pinfunction "A_2") (pintype "input"))
    )
    (net (code "85") (name "Net-(L83-K)") (class "Default")
      (node (ref "L83") (pin "1") (pinfunction "K_1") (pintype "output"))
      (node (ref "L84") (pin "2") (pinfunction "A_2") (pintype "input"))
    )
    (net (code "86") (name "Net-(L84-K)") (class "Default")
      (node (ref "L84") (pin "1") (pinfunction "K_1") (pintype "output"))
      (node (ref "RN7") (pin "6") (pinfunction "2_6") (pintype "passive"))
    )
    (net (code "87") (name "Net-(L85-K)") (class "Default")
      (node (ref "L85") (pin "1") (pinfunction "K_1") (pintype "output"))
      (node (ref "L86") (pin "2") (pinfunction "A_2") (pintype "input"))
    )
    (net (code "88") (name "Net-(L86-K)") (class "Default")
      (node (ref "L86") (pin "1") (pinfunction "K_1") (pintype "output"))
      (node (ref "L87") (pin "2") (pinfunction "A_2") (pintype "input"))
    )
    (net (code "89") (name "Net-(L87-K)") (class "Default")
      (node (ref "L87") (pin "1") (pinfunction "K_1") (pintype "output"))
      (node (ref "RN8") (pin "7") (pinfunction "2_7") (pintype "passive"))
    )
    (net (code "90") (name "Net-(L88-K)") (class "Default")
      (node (ref "L88") (pin "1") (pinfunction "K_1") (pintype "output"))
      (node (ref "L89") (pin "2") (pinfunction "A_2") (pintype "input"))
    )
    (net (code "91") (name "Net-(L89-K)") (class "Default")
      (node (ref "L89") (pin "1") (pinfunction "K_1") (pintype "output"))
      (node (ref "L90") (pin "2") (pinfunction "A_2") (pintype "input"))
    )
    (net (code "92") (name "Net-(L90-K)") (class "Default")
      (node (ref "L90") (pin "1") (pinfunction "K_1") (pintype "output"))
      (node (ref "RN8") (pin "8") (pinfunction "2_8") (pintype "passive"))
    )
    (net (code "93") (name "Net-(L91-K)") (class "Default")
      (node (ref "L91") (pin "1") (pinfunction "K_1") (pintype "output"))
      (node (ref "L92") (pin "2") (pinfunction "A_2") (pintype "input"))
    )
    (net (code "94") (name "Net-(L92-K)") (class "Default")
      (node (ref "L92") (pin "1") (pinfunction "K_1") (pintype "output"))
      (node (ref "L93") (pin "2") (pinfunction "A_2") (pintype "input"))
    )
    (net (code "95") (name "Net-(L93-K)") (class "Default")
      (node (ref "L93") (pin "1") (pinfunction "K_1") (pintype "output"))
      (node (ref "RN8") (pin "5") (pinfunction "2_5") (pintype "passive"))
    )
    (net (code "96") (name "Net-(L94-K)") (class "Default")
      (node (ref "L94") (pin "1") (pinfunction "K_1") (pintype "output"))
      (node (ref "L95") (pin "2") (pinfunction "A_2") (pintype "input"))
    )
    (net (code "97") (name "Net-(L95-K)") (class "Default")
      (node (ref "L95") (pin "1") (pinfunction "K_1") (pintype "output"))
      (node (ref "L96") (pin "2") (pinfunction "A_2") (pintype "input"))
    )
    (net (code "98") (name "Net-(L96-K)") (class "Default")
      (node (ref "L96") (pin "1") (pinfunction "K_1") (pintype "output"))
      (node (ref "RN8") (pin "6") (pinfunction "2_6") (pintype "passive"))
    )
  )
)
